# R2-mechanisms.net
KiCad netlist of a schematic drawn in EAGLE
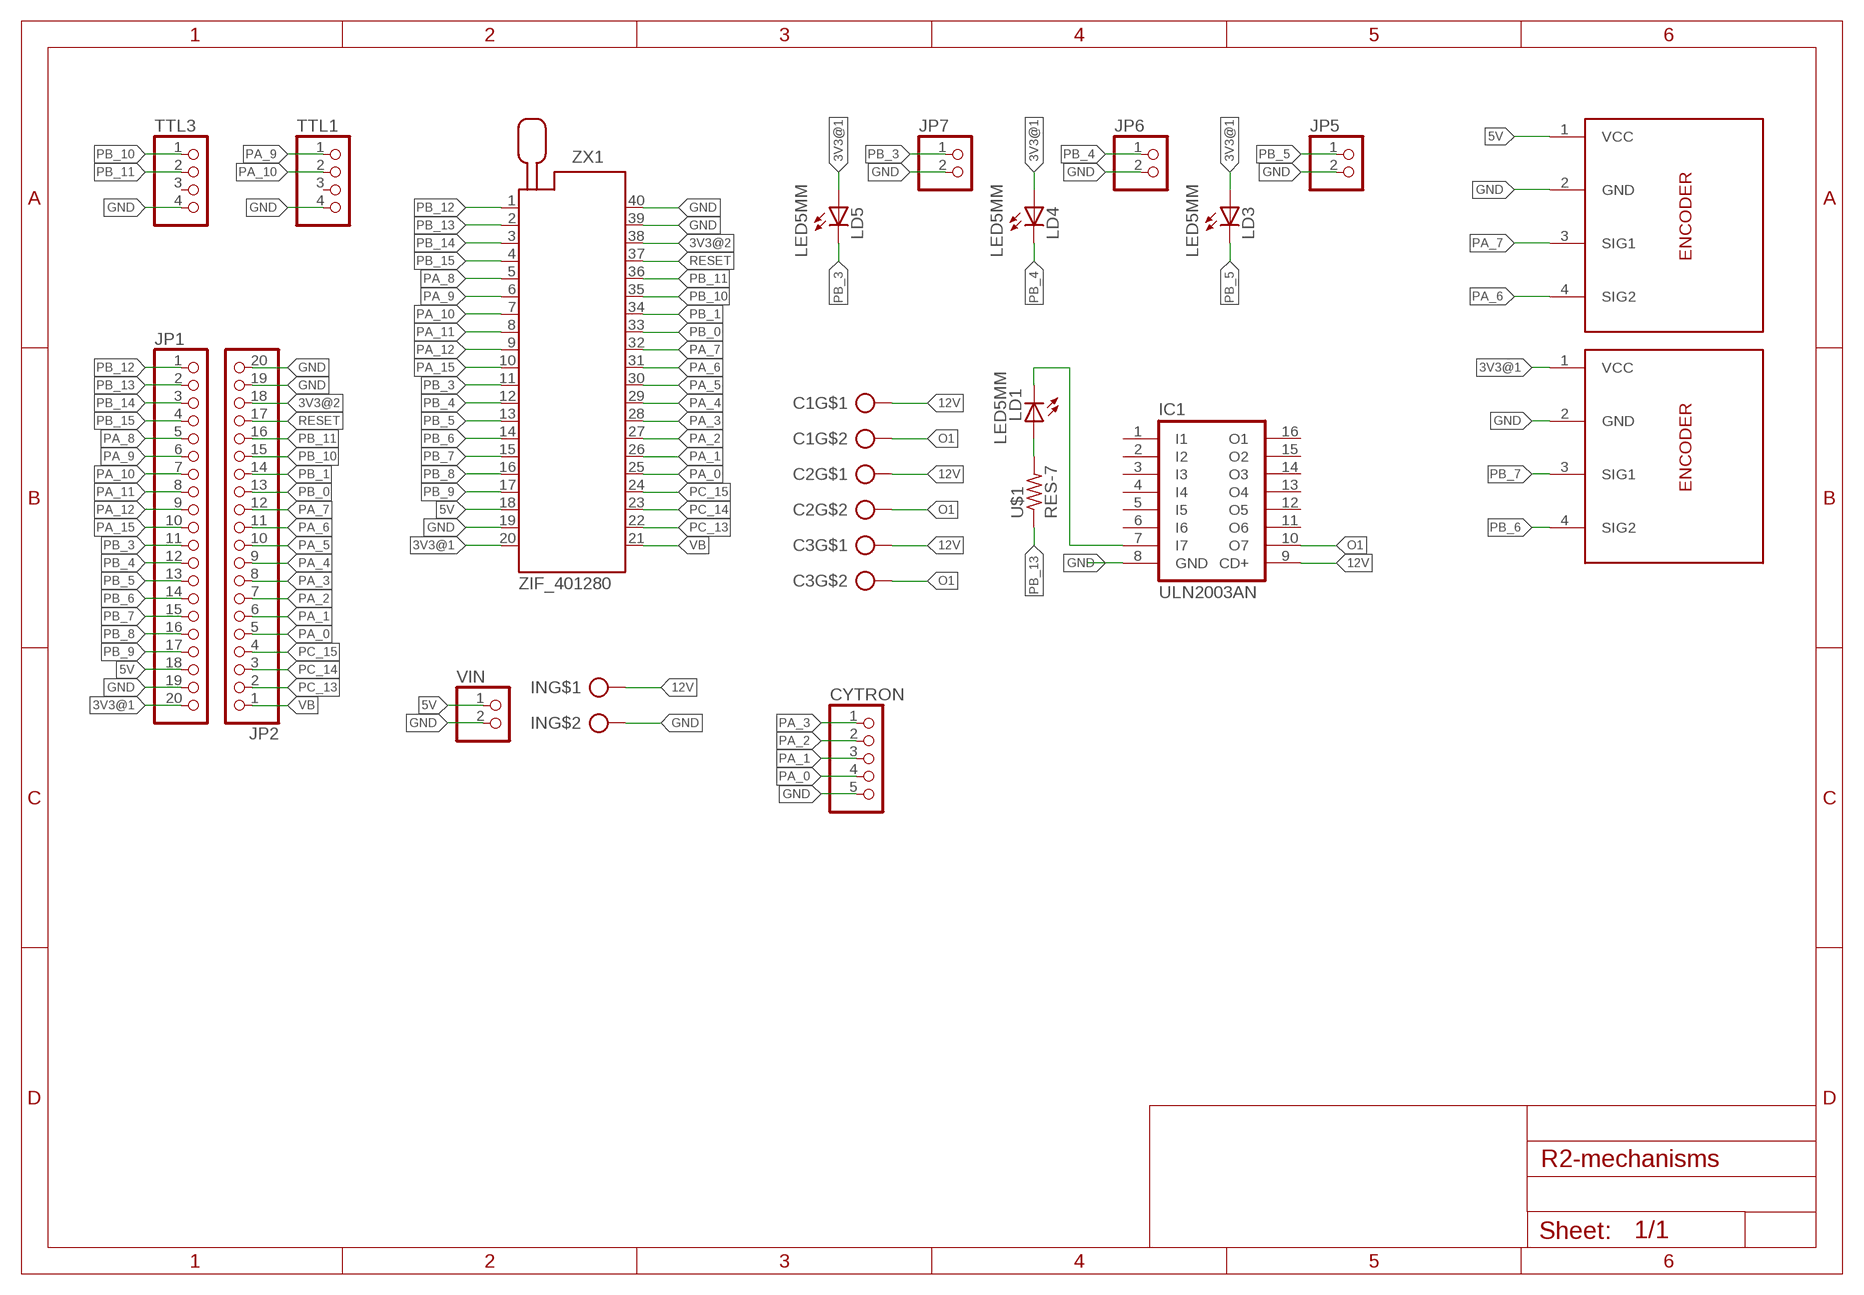
[diagram p0: schematic, sheet 1]

(export (version "E")
  (design (tool "Eeschema 10.0.6"))
  (components
    (comp (ref "C1")
      (value "CON_PTR_2")
      (footprint "eagle-import:AK300_2")
      (libsource (lib "eagle-import") (part "CON_PTR_2"))
    )
    (comp (ref "C2")
      (value "CON_PTR_2")
      (footprint "eagle-import:AK300_2")
      (libsource (lib "eagle-import") (part "CON_PTR_2"))
    )
    (comp (ref "C3")
      (value "CON_PTR_2")
      (footprint "eagle-import:AK300_2")
      (libsource (lib "eagle-import") (part "CON_PTR_2"))
    )
    (comp (ref "CYTRON")
      (value "PINHD-5_DATA")
      (footprint "eagle-import:1X05_DATA")
      (libsource (lib "eagle-import") (part "PINHD-5_DATA"))
    )
    (comp (ref "ENC")
      (value "ENCODER")
      (footprint "eagle-import:1X04_DATA")
      (libsource (lib "eagle-import") (part "ENCODER"))
    )
    (comp (ref "ENC1")
      (value "ENCODER")
      (footprint "eagle-import:1X04_DATA")
      (libsource (lib "eagle-import") (part "ENCODER"))
    )
    (comp (ref "IC1")
      (value "ULN2003AN")
      (footprint "eagle-import:DIL16")
      (libsource (lib "eagle-import") (part "ULN2003AN"))
    )
    (comp (ref "IN")
      (value "CON_PTR_2")
      (footprint "eagle-import:AK300_2")
      (libsource (lib "eagle-import") (part "CON_PTR_2"))
    )
    (comp (ref "JP1")
      (value "PINHD-1X20")
      (footprint "eagle-import:1X20")
      (libsource (lib "eagle-import") (part "PINHD-1X20"))
    )
    (comp (ref "JP2")
      (value "PINHD-1X20")
      (footprint "eagle-import:1X20")
      (libsource (lib "eagle-import") (part "PINHD-1X20"))
    )
    (comp (ref "JP5")
      (value "PINHD-2_DATA")
      (footprint "eagle-import:1X02_DATA")
      (libsource (lib "eagle-import") (part "PINHD-2_DATA"))
    )
    (comp (ref "JP6")
      (value "PINHD-2_DATA")
      (footprint "eagle-import:1X02_DATA")
      (libsource (lib "eagle-import") (part "PINHD-2_DATA"))
    )
    (comp (ref "JP7")
      (value "PINHD-2_DATA")
      (footprint "eagle-import:1X02_DATA")
      (libsource (lib "eagle-import") (part "PINHD-2_DATA"))
    )
    (comp (ref "LD1")
      (value "LED5MM")
      (footprint "eagle-import:LED5MM")
      (libsource (lib "eagle-import") (part "LED5MM"))
    )
    (comp (ref "LD3")
      (value "LED5MM")
      (footprint "eagle-import:LED5MM")
      (libsource (lib "eagle-import") (part "LED5MM"))
    )
    (comp (ref "LD4")
      (value "LED5MM")
      (footprint "eagle-import:LED5MM")
      (libsource (lib "eagle-import") (part "LED5MM"))
    )
    (comp (ref "LD5")
      (value "LED5MM")
      (footprint "eagle-import:LED5MM")
      (libsource (lib "eagle-import") (part "LED5MM"))
    )
    (comp (ref "TTL1")
      (value "PINHD-4_DATA")
      (footprint "eagle-import:1X04_DATA")
      (libsource (lib "eagle-import") (part "PINHD-4_DATA"))
    )
    (comp (ref "TTL3")
      (value "PINHD-4_DATA")
      (footprint "eagle-import:1X04_DATA")
      (libsource (lib "eagle-import") (part "PINHD-4_DATA"))
    )
    (comp (ref "U$1")
      (value "RES-7")
      (footprint "eagle-import:0204_7")
      (libsource (lib "eagle-import") (part "RES-7"))
    )
    (comp (ref "VIN")
      (value "PINHD-2_DATA")
      (footprint "eagle-import:1X02_DATA")
      (libsource (lib "eagle-import") (part "PINHD-2_DATA"))
    )
    (comp (ref "ZX1")
      (value "ZIF_401280")
      (footprint "eagle-import:240-1280-00-0602J")
      (libsource (lib "eagle-import") (part "ZIF_401280"))
    )
  )
  (nets
    (net (code "1") (name "3V3@1") (class "Default")
      (node (ref "ENC1") (pin "1") (pinfunction "VCC_1") (pintype "bidirectional"))
      (node (ref "JP1") (pin "20") (pinfunction "20_20") (pintype "passive"))
      (node (ref "LD3") (pin "A") (pinfunction "A_A") (pintype "passive"))
      (node (ref "LD4") (pin "A") (pinfunction "A_A") (pintype "passive"))
      (node (ref "LD5") (pin "A") (pinfunction "A_A") (pintype "passive"))
      (node (ref "ZX1") (pin "20") (pinfunction "20_20") (pintype "passive"))
    )
    (net (code "2") (name "3V3@2") (class "Default")
      (node (ref "JP2") (pin "18") (pinfunction "18_18") (pintype "passive"))
      (node (ref "ZX1") (pin "38") (pinfunction "38_38") (pintype "passive"))
    )
    (net (code "3") (name "5V") (class "Default")
      (node (ref "ENC") (pin "1") (pinfunction "VCC_1") (pintype "bidirectional"))
      (node (ref "JP1") (pin "18") (pinfunction "18_18") (pintype "passive"))
      (node (ref "VIN") (pin "1") (pinfunction "1_1") (pintype "passive"))
      (node (ref "ZX1") (pin "18") (pinfunction "18_18") (pintype "passive"))
    )
    (net (code "4") (name "12V") (class "Default")
      (node (ref "C1") (pin "1") (pinfunction "KL_1") (pintype "passive"))
      (node (ref "C2") (pin "1") (pinfunction "KL_1") (pintype "passive"))
      (node (ref "C3") (pin "1") (pinfunction "KL_1") (pintype "passive"))
      (node (ref "IC1") (pin "9") (pinfunction "CD+_9") (pintype "passive"))
      (node (ref "IN") (pin "1") (pinfunction "KL_1") (pintype "passive"))
    )
    (net (code "5") (name "GND") (class "Default")
      (node (ref "CYTRON") (pin "5") (pinfunction "5_5") (pintype "passive"))
      (node (ref "ENC") (pin "2") (pinfunction "GND_2") (pintype "bidirectional"))
      (node (ref "ENC1") (pin "2") (pinfunction "GND_2") (pintype "bidirectional"))
      (node (ref "IC1") (pin "8") (pinfunction "GND_8") (pintype "power_in"))
      (node (ref "IN") (pin "2") (pinfunction "KL_2") (pintype "passive"))
      (node (ref "JP1") (pin "19") (pinfunction "19_19") (pintype "passive"))
      (node (ref "JP2") (pin "19") (pinfunction "19_19") (pintype "passive"))
      (node (ref "JP2") (pin "20") (pinfunction "20_20") (pintype "passive"))
      (node (ref "JP5") (pin "2") (pinfunction "2_2") (pintype "passive"))
      (node (ref "JP6") (pin "2") (pinfunction "2_2") (pintype "passive"))
      (node (ref "JP7") (pin "2") (pinfunction "2_2") (pintype "passive"))
      (node (ref "TTL1") (pin "4") (pinfunction "4_4") (pintype "passive"))
      (node (ref "TTL3") (pin "4") (pinfunction "4_4") (pintype "passive"))
      (node (ref "VIN") (pin "2") (pinfunction "2_2") (pintype "passive"))
      (node (ref "ZX1") (pin "19") (pinfunction "19_19") (pintype "passive"))
      (node (ref "ZX1") (pin "39") (pinfunction "39_39") (pintype "passive"))
      (node (ref "ZX1") (pin "40") (pinfunction "40_40") (pintype "passive"))
    )
    (net (code "6") (name "Net-(IC1-I7)") (class "Default")
      (node (ref "IC1") (pin "7") (pinfunction "I7_7") (pintype "input"))
      (node (ref "LD1") (pin "K") (pinfunction "C_K") (pintype "passive"))
    )
    (net (code "7") (name "Net-(LD1-PadA)") (class "Default")
      (node (ref "LD1") (pin "A") (pinfunction "A_A") (pintype "passive"))
      (node (ref "U$1") (pin "2") (pinfunction "2_2") (pintype "passive"))
    )
    (net (code "8") (name "O1") (class "Default")
      (node (ref "C1") (pin "2") (pinfunction "KL_2") (pintype "passive"))
      (node (ref "C2") (pin "2") (pinfunction "KL_2") (pintype "passive"))
      (node (ref "C3") (pin "2") (pinfunction "KL_2") (pintype "passive"))
      (node (ref "IC1") (pin "10") (pinfunction "O7_10") (pintype "open_collector"))
    )
    (net (code "9") (name "PA_0") (class "Default")
      (node (ref "CYTRON") (pin "4") (pinfunction "4_4") (pintype "passive"))
      (node (ref "JP2") (pin "5") (pinfunction "5_5") (pintype "passive"))
      (node (ref "ZX1") (pin "25") (pinfunction "25_25") (pintype "passive"))
    )
    (net (code "10") (name "PA_1") (class "Default")
      (node (ref "CYTRON") (pin "3") (pinfunction "3_3") (pintype "passive"))
      (node (ref "JP2") (pin "6") (pinfunction "6_6") (pintype "passive"))
      (node (ref "ZX1") (pin "26") (pinfunction "26_26") (pintype "passive"))
    )
    (net (code "11") (name "PA_2") (class "Default")
      (node (ref "CYTRON") (pin "2") (pinfunction "2_2") (pintype "passive"))
      (node (ref "JP2") (pin "7") (pinfunction "7_7") (pintype "passive"))
      (node (ref "ZX1") (pin "27") (pinfunction "27_27") (pintype "passive"))
    )
    (net (code "12") (name "PA_3") (class "Default")
      (node (ref "CYTRON") (pin "1") (pinfunction "1_1") (pintype "passive"))
      (node (ref "JP2") (pin "8") (pinfunction "8_8") (pintype "passive"))
      (node (ref "ZX1") (pin "28") (pinfunction "28_28") (pintype "passive"))
    )
    (net (code "13") (name "PA_4") (class "Default")
      (node (ref "JP2") (pin "9") (pinfunction "9_9") (pintype "passive"))
      (node (ref "ZX1") (pin "29") (pinfunction "29_29") (pintype "passive"))
    )
    (net (code "14") (name "PA_5") (class "Default")
      (node (ref "JP2") (pin "10") (pinfunction "10_10") (pintype "passive"))
      (node (ref "ZX1") (pin "30") (pinfunction "30_30") (pintype "passive"))
    )
    (net (code "15") (name "PA_6") (class "Default")
      (node (ref "ENC") (pin "4") (pinfunction "SIG2_4") (pintype "bidirectional"))
      (node (ref "JP2") (pin "11") (pinfunction "11_11") (pintype "passive"))
      (node (ref "ZX1") (pin "31") (pinfunction "31_31") (pintype "passive"))
    )
    (net (code "16") (name "PA_7") (class "Default")
      (node (ref "ENC") (pin "3") (pinfunction "SIG1_3") (pintype "bidirectional"))
      (node (ref "JP2") (pin "12") (pinfunction "12_12") (pintype "passive"))
      (node (ref "ZX1") (pin "32") (pinfunction "32_32") (pintype "passive"))
    )
    (net (code "17") (name "PA_8") (class "Default")
      (node (ref "JP1") (pin "5") (pinfunction "5_5") (pintype "passive"))
      (node (ref "ZX1") (pin "5") (pinfunction "5_5") (pintype "passive"))
    )
    (net (code "18") (name "PA_9") (class "Default")
      (node (ref "JP1") (pin "6") (pinfunction "6_6") (pintype "passive"))
      (node (ref "TTL1") (pin "1") (pinfunction "1_1") (pintype "passive"))
      (node (ref "ZX1") (pin "6") (pinfunction "6_6") (pintype "passive"))
    )
    (net (code "19") (name "PA_10") (class "Default")
      (node (ref "JP1") (pin "7") (pinfunction "7_7") (pintype "passive"))
      (node (ref "TTL1") (pin "2") (pinfunction "2_2") (pintype "passive"))
      (node (ref "ZX1") (pin "7") (pinfunction "7_7") (pintype "passive"))
    )
    (net (code "20") (name "PA_11") (class "Default")
      (node (ref "JP1") (pin "8") (pinfunction "8_8") (pintype "passive"))
      (node (ref "ZX1") (pin "8") (pinfunction "8_8") (pintype "passive"))
    )
    (net (code "21") (name "PA_12") (class "Default")
      (node (ref "JP1") (pin "9") (pinfunction "9_9") (pintype "passive"))
      (node (ref "ZX1") (pin "9") (pinfunction "9_9") (pintype "passive"))
    )
    (net (code "22") (name "PA_15") (class "Default")
      (node (ref "JP1") (pin "10") (pinfunction "10_10") (pintype "passive"))
      (node (ref "ZX1") (pin "10") (pinfunction "10_10") (pintype "passive"))
    )
    (net (code "23") (name "PB_0") (class "Default")
      (node (ref "JP2") (pin "13") (pinfunction "13_13") (pintype "passive"))
      (node (ref "ZX1") (pin "33") (pinfunction "33_33") (pintype "passive"))
    )
    (net (code "24") (name "PB_1") (class "Default")
      (node (ref "JP2") (pin "14") (pinfunction "14_14") (pintype "passive"))
      (node (ref "ZX1") (pin "34") (pinfunction "34_34") (pintype "passive"))
    )
    (net (code "25") (name "PB_3") (class "Default")
      (node (ref "JP1") (pin "11") (pinfunction "11_11") (pintype "passive"))
      (node (ref "JP7") (pin "1") (pinfunction "1_1") (pintype "passive"))
      (node (ref "LD5") (pin "K") (pinfunction "C_K") (pintype "passive"))
      (node (ref "ZX1") (pin "11") (pinfunction "11_11") (pintype "passive"))
    )
    (net (code "26") (name "PB_4") (class "Default")
      (node (ref "JP1") (pin "12") (pinfunction "12_12") (pintype "passive"))
      (node (ref "JP6") (pin "1") (pinfunction "1_1") (pintype "passive"))
      (node (ref "LD4") (pin "K") (pinfunction "C_K") (pintype "passive"))
      (node (ref "ZX1") (pin "12") (pinfunction "12_12") (pintype "passive"))
    )
    (net (code "27") (name "PB_5") (class "Default")
      (node (ref "JP1") (pin "13") (pinfunction "13_13") (pintype "passive"))
      (node (ref "JP5") (pin "1") (pinfunction "1_1") (pintype "passive"))
      (node (ref "LD3") (pin "K") (pinfunction "C_K") (pintype "passive"))
      (node (ref "ZX1") (pin "13") (pinfunction "13_13") (pintype "passive"))
    )
    (net (code "28") (name "PB_6") (class "Default")
      (node (ref "ENC1") (pin "4") (pinfunction "SIG2_4") (pintype "bidirectional"))
      (node (ref "JP1") (pin "14") (pinfunction "14_14") (pintype "passive"))
      (node (ref "ZX1") (pin "14") (pinfunction "14_14") (pintype "passive"))
    )
    (net (code "29") (name "PB_7") (class "Default")
      (node (ref "ENC1") (pin "3") (pinfunction "SIG1_3") (pintype "bidirectional"))
      (node (ref "JP1") (pin "15") (pinfunction "15_15") (pintype "passive"))
      (node (ref "ZX1") (pin "15") (pinfunction "15_15") (pintype "passive"))
    )
    (net (code "30") (name "PB_8") (class "Default")
      (node (ref "JP1") (pin "16") (pinfunction "16_16") (pintype "passive"))
      (node (ref "ZX1") (pin "16") (pinfunction "16_16") (pintype "passive"))
    )
    (net (code "31") (name "PB_9") (class "Default")
      (node (ref "JP1") (pin "17") (pinfunction "17_17") (pintype "passive"))
      (node (ref "ZX1") (pin "17") (pinfunction "17_17") (pintype "passive"))
    )
    (net (code "32") (name "PB_10") (class "Default")
      (node (ref "JP2") (pin "15") (pinfunction "15_15") (pintype "passive"))
      (node (ref "TTL3") (pin "1") (pinfunction "1_1") (pintype "passive"))
      (node (ref "ZX1") (pin "35") (pinfunction "35_35") (pintype "passive"))
    )
    (net (code "33") (name "PB_11") (class "Default")
      (node (ref "JP2") (pin "16") (pinfunction "16_16") (pintype "passive"))
      (node (ref "TTL3") (pin "2") (pinfunction "2_2") (pintype "passive"))
      (node (ref "ZX1") (pin "36") (pinfunction "36_36") (pintype "passive"))
    )
    (net (code "34") (name "PB_12") (class "Default")
      (node (ref "JP1") (pin "1") (pinfunction "1_1") (pintype "passive"))
      (node (ref "ZX1") (pin "1") (pinfunction "1_1") (pintype "passive"))
    )
    (net (code "35") (name "PB_13") (class "Default")
      (node (ref "JP1") (pin "2") (pinfunction "2_2") (pintype "passive"))
      (node (ref "U$1") (pin "1") (pinfunction "1_1") (pintype "passive"))
      (node (ref "ZX1") (pin "2") (pinfunction "2_2") (pintype "passive"))
    )
    (net (code "36") (name "PB_14") (class "Default")
      (node (ref "JP1") (pin "3") (pinfunction "3_3") (pintype "passive"))
      (node (ref "ZX1") (pin "3") (pinfunction "3_3") (pintype "passive"))
    )
    (net (code "37") (name "PB_15") (class "Default")
      (node (ref "JP1") (pin "4") (pinfunction "4_4") (pintype "passive"))
      (node (ref "ZX1") (pin "4") (pinfunction "4_4") (pintype "passive"))
    )
    (net (code "38") (name "PC_13") (class "Default")
      (node (ref "JP2") (pin "2") (pinfunction "2_2") (pintype "passive"))
      (node (ref "ZX1") (pin "22") (pinfunction "22_22") (pintype "passive"))
    )
    (net (code "39") (name "PC_14") (class "Default")
      (node (ref "JP2") (pin "3") (pinfunction "3_3") (pintype "passive"))
      (node (ref "ZX1") (pin "23") (pinfunction "23_23") (pintype "passive"))
    )
    (net (code "40") (name "PC_15") (class "Default")
      (node (ref "JP2") (pin "4") (pinfunction "4_4") (pintype "passive"))
      (node (ref "ZX1") (pin "24") (pinfunction "24_24") (pintype "passive"))
    )
    (net (code "41") (name "RESET") (class "Default")
      (node (ref "JP2") (pin "17") (pinfunction "17_17") (pintype "passive"))
      (node (ref "ZX1") (pin "37") (pinfunction "37_37") (pintype "passive"))
    )
    (net (code "42") (name "VB") (class "Default")
      (node (ref "JP2") (pin "1") (pinfunction "1_1") (pintype "passive"))
      (node (ref "ZX1") (pin "21") (pinfunction "21_21") (pintype "passive"))
    )
    (net (code "43") (name "unconnected-(IC1-I1-Pad1)") (class "Default")
      (node (ref "IC1") (pin "1") (pinfunction "I1_1") (pintype "input"))
    )
    (net (code "44") (name "unconnected-(IC1-I2-Pad2)") (class "Default")
      (node (ref "IC1") (pin "2") (pinfunction "I2_2") (pintype "input"))
    )
    (net (code "45") (name "unconnected-(IC1-I3-Pad3)") (class "Default")
      (node (ref "IC1") (pin "3") (pinfunction "I3_3") (pintype "input"))
    )
    (net (code "46") (name "unconnected-(IC1-I4-Pad4)") (class "Default")
      (node (ref "IC1") (pin "4") (pinfunction "I4_4") (pintype "input"))
    )
    (net (code "47") (name "unconnected-(IC1-I5-Pad5)") (class "Default")
      (node (ref "IC1") (pin "5") (pinfunction "I5_5") (pintype "input"))
    )
    (net (code "48") (name "unconnected-(IC1-I6-Pad6)") (class "Default")
      (node (ref "IC1") (pin "6") (pinfunction "I6_6") (pintype "input"))
    )
    (net (code "49") (name "unconnected-(IC1-O1-Pad16)") (class "Default")
      (node (ref "IC1") (pin "16") (pinfunction "O1_16") (pintype "open_collector"))
    )
    (net (code "50") (name "unconnected-(IC1-O2-Pad15)") (class "Default")
      (node (ref "IC1") (pin "15") (pinfunction "O2_15") (pintype "open_collector"))
    )
    (net (code "51") (name "unconnected-(IC1-O3-Pad14)") (class "Default")
      (node (ref "IC1") (pin "14") (pinfunction "O3_14") (pintype "open_collector"))
    )
    (net (code "52") (name "unconnected-(IC1-O4-Pad13)") (class "Default")
      (node (ref "IC1") (pin "13") (pinfunction "O4_13") (pintype "open_collector"))
    )
    (net (code "53") (name "unconnected-(IC1-O5-Pad12)") (class "Default")
      (node (ref "IC1") (pin "12") (pinfunction "O5_12") (pintype "open_collector"))
    )
    (net (code "54") (name "unconnected-(IC1-O6-Pad11)") (class "Default")
      (node (ref "IC1") (pin "11") (pinfunction "O6_11") (pintype "open_collector"))
    )
    (net (code "55") (name "unconnected-(TTL1-Pad3)") (class "Default")
      (node (ref "TTL1") (pin "3") (pinfunction "3_3") (pintype "passive"))
    )
    (net (code "56") (name "unconnected-(TTL3-Pad3)") (class "Default")
      (node (ref "TTL3") (pin "3") (pinfunction "3_3") (pintype "passive"))
    )
  )
)
